# 80_TY_Zigbee.net
KiCad netlist of a schematic drawn in Altium Designer
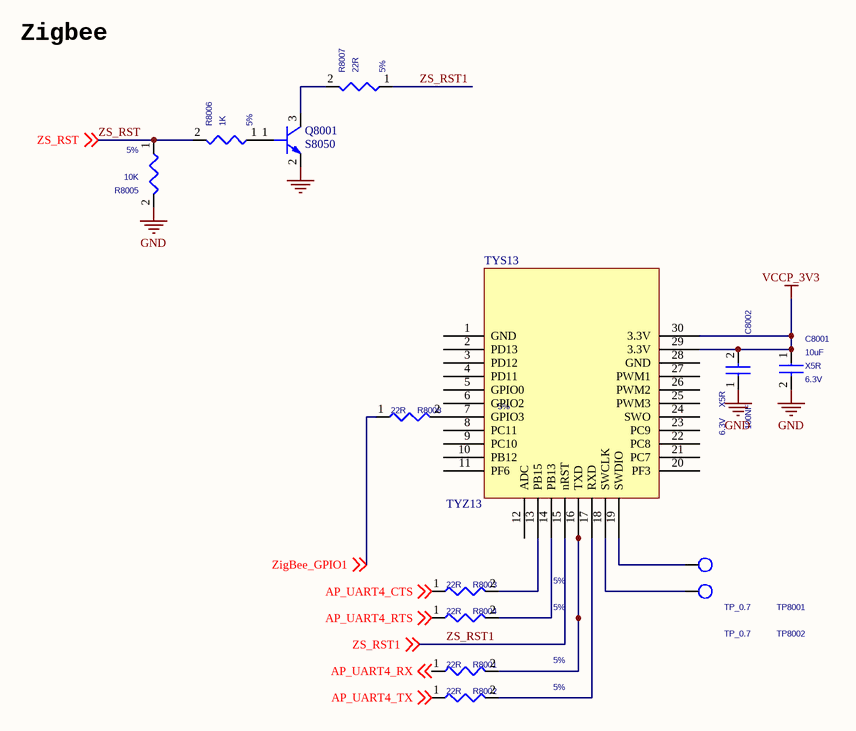
[diagram p0: 80_TY_Zigbee.SchDoc]

(export (version "E")
  (design (tool "Eeschema 10.0.6"))
  (components
    (comp (ref "C8001")
      (value "10uF")
      (footprint "C0603")
      (description "cap,10uF,+/-20%,6.3V,X5R,C0603")
      (fields
        (field (name "VOLTAGE") "6.3V")
        (field (name "DIELECTRIC") "X5R")
        (field (name "MANUFACTURER") "TDK")
        (field (name "TOLERANCE") "20%")
        (field (name "CREATED BY") "JJJ")
      )
      (libsource (lib "*") (part "CAP NP_Dup1"))
    )
    (comp (ref "C8002")
      (value "100NF")
      (footprint "C0402")
      (description "cap,100.00nF,+/-10%,6.3V,X5R,C0402")
      (fields
        (field (name "VOLTAGE") "6.3V")
        (field (name "DIELECTRIC") "X5R")
        (field (name "MANUFACTURER") "TDK")
        (field (name "TOLERANCE") "10%")
        (field (name "CREATED BY") "JJJ")
      )
      (libsource (lib "*") (part "CAP NP_Dup1"))
    )
    (comp (ref "Q8001")
      (value "S8050")
      (footprint "SOT23")
      (libsource (lib "PX30_REF_V14_20200721_Library") (part "NPN"))
    )
    (comp (ref "R8001")
      (value "22R")
      (footprint "R0402")
      (description "通用厚膜电阻,22R,+/-5%,R0402,1/16W.")
      (fields
        (field (name "TOLERANCE") "5%")
        (field (name "MANUFACTURER") "YAGEO")
        (field (name "CREATED BY") "YTL")
      )
      (libsource (lib "*") (part "RESISTOR_Dup1"))
    )
    (comp (ref "R8002")
      (value "22R")
      (footprint "R0402")
      (description "通用厚膜电阻,22R,+/-5%,R0402,1/16W.")
      (fields
        (field (name "TOLERANCE") "5%")
        (field (name "MANUFACTURER") "YAGEO")
        (field (name "CREATED BY") "YTL")
      )
      (libsource (lib "*") (part "RESISTOR_Dup1"))
    )
    (comp (ref "R8003")
      (value "22R")
      (footprint "R0402")
      (description "通用厚膜电阻,22R,+/-5%,R0402,1/16W.")
      (fields
        (field (name "TOLERANCE") "5%")
        (field (name "MANUFACTURER") "YAGEO")
        (field (name "CREATED BY") "YTL")
      )
      (libsource (lib "*") (part "RESISTOR_Dup1"))
    )
    (comp (ref "R8004")
      (value "22R")
      (footprint "R0402")
      (description "通用厚膜电阻,22R,+/-5%,R0402,1/16W.")
      (fields
        (field (name "TOLERANCE") "5%")
        (field (name "MANUFACTURER") "YAGEO")
        (field (name "CREATED BY") "YTL")
      )
      (libsource (lib "*") (part "RESISTOR_Dup1"))
    )
    (comp (ref "R8005")
      (value "10K")
      (footprint "R0402")
      (description "通用厚膜电阻,1K,+/-5%,R0402,1/16W.")
      (fields
        (field (name "TOLERANCE") "5%")
        (field (name "MANUFACTURER") "YAGEO")
        (field (name "CREATED BY") "YTL")
      )
      (libsource (lib "*") (part "RESISTOR_Dup1"))
    )
    (comp (ref "R8006")
      (value "1K")
      (footprint "R0402")
      (description "通用厚膜电阻,1K,+/-5%,R0402,1/16W.")
      (fields
        (field (name "TOLERANCE") "5%")
        (field (name "MANUFACTURER") "YAGEO")
        (field (name "CREATED BY") "YTL")
      )
      (libsource (lib "*") (part "RESISTOR_Dup1"))
    )
    (comp (ref "R8007")
      (value "22R")
      (footprint "R0402")
      (description "通用厚膜电阻,22R,+/-5%,R0402,1/16W.")
      (fields
        (field (name "TOLERANCE") "5%")
        (field (name "MANUFACTURER") "YAGEO")
        (field (name "CREATED BY") "YTL")
      )
      (libsource (lib "*") (part "RESISTOR_Dup1"))
    )
    (comp (ref "R8008")
      (value "22R")
      (footprint "R0402")
      (description "通用厚膜电阻,22R,+/-5%,R0402,1/16W.")
      (fields
        (field (name "TOLERANCE") "5%")
        (field (name "MANUFACTURER") "YAGEO")
        (field (name "CREATED BY") "YTL")
      )
      (libsource (lib "*") (part "RESISTOR_Dup1"))
    )
    (comp (ref "TP8001")
      (value "TP_0.7")
      (footprint "TEST")
      (description "Test Point 0.7mm")
      (fields (field (name "CREATED BY") "JJJ"))
      (libsource (lib "*") (part "TP"))
    )
    (comp (ref "TP8002")
      (value "TP_0.7")
      (footprint "TEST")
      (description "Test Point 0.7mm")
      (fields (field (name "CREATED BY") "JJJ"))
      (libsource (lib "*") (part "TP"))
    )
    (comp (ref "TYS13") (value "TYZ13") (footprint "TYS13") (libsource (lib "amenuo") (part "TYZS13")))
  )
  (nets
    (net (code "1") (name "AP_UART4_CTS") (class "Default")
      (node (ref "R8003") (pin "1") (pinfunction "1_1") (pintype "passive"))
    )
    (net (code "2") (name "AP_UART4_RTS") (class "Default")
      (node (ref "R8004") (pin "1") (pinfunction "1_1") (pintype "passive"))
    )
    (net (code "3") (name "AP_UART4_RX") (class "Default")
      (node (ref "R8001") (pin "1") (pinfunction "1_1") (pintype "passive"))
    )
    (net (code "4") (name "AP_UART4_TX") (class "Default")
      (node (ref "R8002") (pin "1") (pinfunction "1_1") (pintype "passive"))
    )
    (net (code "5") (name "GND") (class "Default")
      (node (ref "C8001") (pin "2") (pinfunction "2_2") (pintype "passive"))
      (node (ref "C8002") (pin "1") (pinfunction "1_1") (pintype "passive"))
      (node (ref "Q8001") (pin "2") (pinfunction "EMITTER_2") (pintype "passive"))
      (node (ref "R8005") (pin "2") (pinfunction "2_2") (pintype "passive"))
    )
    (net (code "6") (name "Net-(Q8001-BASE)") (class "Default")
      (node (ref "Q8001") (pin "1") (pinfunction "BASE_1") (pintype "passive"))
      (node (ref "R8006") (pin "1") (pinfunction "1_1") (pintype "passive"))
    )
    (net (code "7") (name "Net-(Q8001-COLLECTOR)") (class "Default")
      (node (ref "Q8001") (pin "3") (pinfunction "COLLECTOR_3") (pintype "passive"))
      (node (ref "R8007") (pin "2") (pinfunction "2_2") (pintype "passive"))
    )
    (net (code "8") (name "Net-(TYS13-GPIO3)") (class "Default")
      (node (ref "R8008") (pin "2") (pinfunction "2_2") (pintype "passive"))
      (node (ref "TYS13") (pin "7") (pinfunction "GPIO3_7") (pintype "passive"))
    )
    (net (code "9") (name "Net-(TYS13-PB13)") (class "Default")
      (node (ref "R8004") (pin "2") (pinfunction "2_2") (pintype "passive"))
      (node (ref "TYS13") (pin "14") (pinfunction "PB13_14") (pintype "passive"))
    )
    (net (code "10") (name "Net-(TYS13-PB15)") (class "Default")
      (node (ref "R8003") (pin "2") (pinfunction "2_2") (pintype "passive"))
      (node (ref "TYS13") (pin "13") (pinfunction "PB15_13") (pintype "passive"))
    )
    (net (code "11") (name "Net-(TYS13-RXD)") (class "Default")
      (node (ref "R8002") (pin "2") (pinfunction "2_2") (pintype "passive"))
      (node (ref "TYS13") (pin "17") (pinfunction "RXD_17") (pintype "passive"))
    )
    (net (code "12") (name "Net-(TYS13-SWCLK)") (class "Default")
      (node (ref "TP8002") (pin "1") (pinfunction "1_1") (pintype "passive"))
      (node (ref "TYS13") (pin "18") (pinfunction "SWCLK_18") (pintype "passive"))
    )
    (net (code "13") (name "Net-(TYS13-SWDIO)") (class "Default")
      (node (ref "TP8001") (pin "1") (pinfunction "1_1") (pintype "passive"))
      (node (ref "TYS13") (pin "19") (pinfunction "SWDIO_19") (pintype "passive"))
    )
    (net (code "14") (name "Net-(TYS13-TXD)") (class "Default")
      (node (ref "R8001") (pin "2") (pinfunction "2_2") (pintype "passive"))
      (node (ref "TYS13") (pin "16") (pinfunction "TXD_16") (pintype "passive"))
    )
    (net (code "15") (name "VCCP_3V3") (class "Default")
      (node (ref "C8001") (pin "1") (pinfunction "1_1") (pintype "passive"))
      (node (ref "C8002") (pin "2") (pinfunction "2_2") (pintype "passive"))
      (node (ref "TYS13") (pin "29") (pinfunction "3.3V_29") (pintype "passive"))
      (node (ref "TYS13") (pin "30") (pinfunction "3.3V_30") (pintype "passive"))
    )
    (net (code "16") (name "ZS_RST") (class "Default")
      (node (ref "R8005") (pin "1") (pinfunction "1_1") (pintype "passive"))
      (node (ref "R8006") (pin "2") (pinfunction "2_2") (pintype "passive"))
    )
    (net (code "17") (name "ZS_RST1") (class "Default")
      (node (ref "R8007") (pin "1") (pinfunction "1_1") (pintype "passive"))
      (node (ref "TYS13") (pin "15") (pinfunction "nRST_15") (pintype "passive"))
    )
    (net (code "18") (name "ZigBee_GPIO1") (class "Default")
      (node (ref "R8008") (pin "1") (pinfunction "1_1") (pintype "passive"))
    )
    (net (code "19") (name "unconnected-(TYS13-ADC-Pad12)") (class "Default")
      (node (ref "TYS13") (pin "12") (pinfunction "ADC_12") (pintype "passive"))
    )
    (net (code "20") (name "unconnected-(TYS13-GND-Pad1)") (class "Default")
      (node (ref "TYS13") (pin "1") (pinfunction "GND_1") (pintype "passive"))
    )
    (net (code "21") (name "unconnected-(TYS13-GND-Pad28)") (class "Default")
      (node (ref "TYS13") (pin "28") (pinfunction "GND_28") (pintype "passive"))
    )
    (net (code "22") (name "unconnected-(TYS13-GPIO0-Pad5)") (class "Default")
      (node (ref "TYS13") (pin "5") (pinfunction "GPIO0_5") (pintype "passive"))
    )
    (net (code "23") (name "unconnected-(TYS13-GPIO2-Pad6)") (class "Default")
      (node (ref "TYS13") (pin "6") (pinfunction "GPIO2_6") (pintype "passive"))
    )
    (net (code "24") (name "unconnected-(TYS13-PB12-Pad10)") (class "Default")
      (node (ref "TYS13") (pin "10") (pinfunction "PB12_10") (pintype "passive"))
    )
    (net (code "25") (name "unconnected-(TYS13-PC7-Pad21)") (class "Default")
      (node (ref "TYS13") (pin "21") (pinfunction "PC7_21") (pintype "passive"))
    )
    (net (code "26") (name "unconnected-(TYS13-PC8-Pad22)") (class "Default")
      (node (ref "TYS13") (pin "22") (pinfunction "PC8_22") (pintype "passive"))
    )
    (net (code "27") (name "unconnected-(TYS13-PC9-Pad23)") (class "Default")
      (node (ref "TYS13") (pin "23") (pinfunction "PC9_23") (pintype "passive"))
    )
    (net (code "28") (name "unconnected-(TYS13-PC10-Pad9)") (class "Default")
      (node (ref "TYS13") (pin "9") (pinfunction "PC10_9") (pintype "passive"))
    )
    (net (code "29") (name "unconnected-(TYS13-PC11-Pad8)") (class "Default")
      (node (ref "TYS13") (pin "8") (pinfunction "PC11_8") (pintype "passive"))
    )
    (net (code "30") (name "unconnected-(TYS13-PD11-Pad4)") (class "Default")
      (node (ref "TYS13") (pin "4") (pinfunction "PD11_4") (pintype "passive"))
    )
    (net (code "31") (name "unconnected-(TYS13-PD12-Pad3)") (class "Default")
      (node (ref "TYS13") (pin "3") (pinfunction "PD12_3") (pintype "passive"))
    )
    (net (code "32") (name "unconnected-(TYS13-PD13-Pad2)") (class "Default")
      (node (ref "TYS13") (pin "2") (pinfunction "PD13_2") (pintype "passive"))
    )
    (net (code "33") (name "unconnected-(TYS13-PF3-Pad20)") (class "Default")
      (node (ref "TYS13") (pin "20") (pinfunction "PF3_20") (pintype "passive"))
    )
    (net (code "34") (name "unconnected-(TYS13-PF6-Pad11)") (class "Default")
      (node (ref "TYS13") (pin "11") (pinfunction "PF6_11") (pintype "passive"))
    )
    (net (code "35") (name "unconnected-(TYS13-PWM1-Pad27)") (class "Default")
      (node (ref "TYS13") (pin "27") (pinfunction "PWM1_27") (pintype "passive"))
    )
    (net (code "36") (name "unconnected-(TYS13-PWM2-Pad26)") (class "Default")
      (node (ref "TYS13") (pin "26") (pinfunction "PWM2_26") (pintype "passive"))
    )
    (net (code "37") (name "unconnected-(TYS13-PWM3-Pad25)") (class "Default")
      (node (ref "TYS13") (pin "25") (pinfunction "PWM3_25") (pintype "passive"))
    )
    (net (code "38") (name "unconnected-(TYS13-SWO-Pad24)") (class "Default")
      (node (ref "TYS13") (pin "24") (pinfunction "SWO_24") (pintype "passive"))
    )
  )
)
